# FX-NVBMP_rev_A.net
KiCad netlist of a schematic drawn in EAGLE
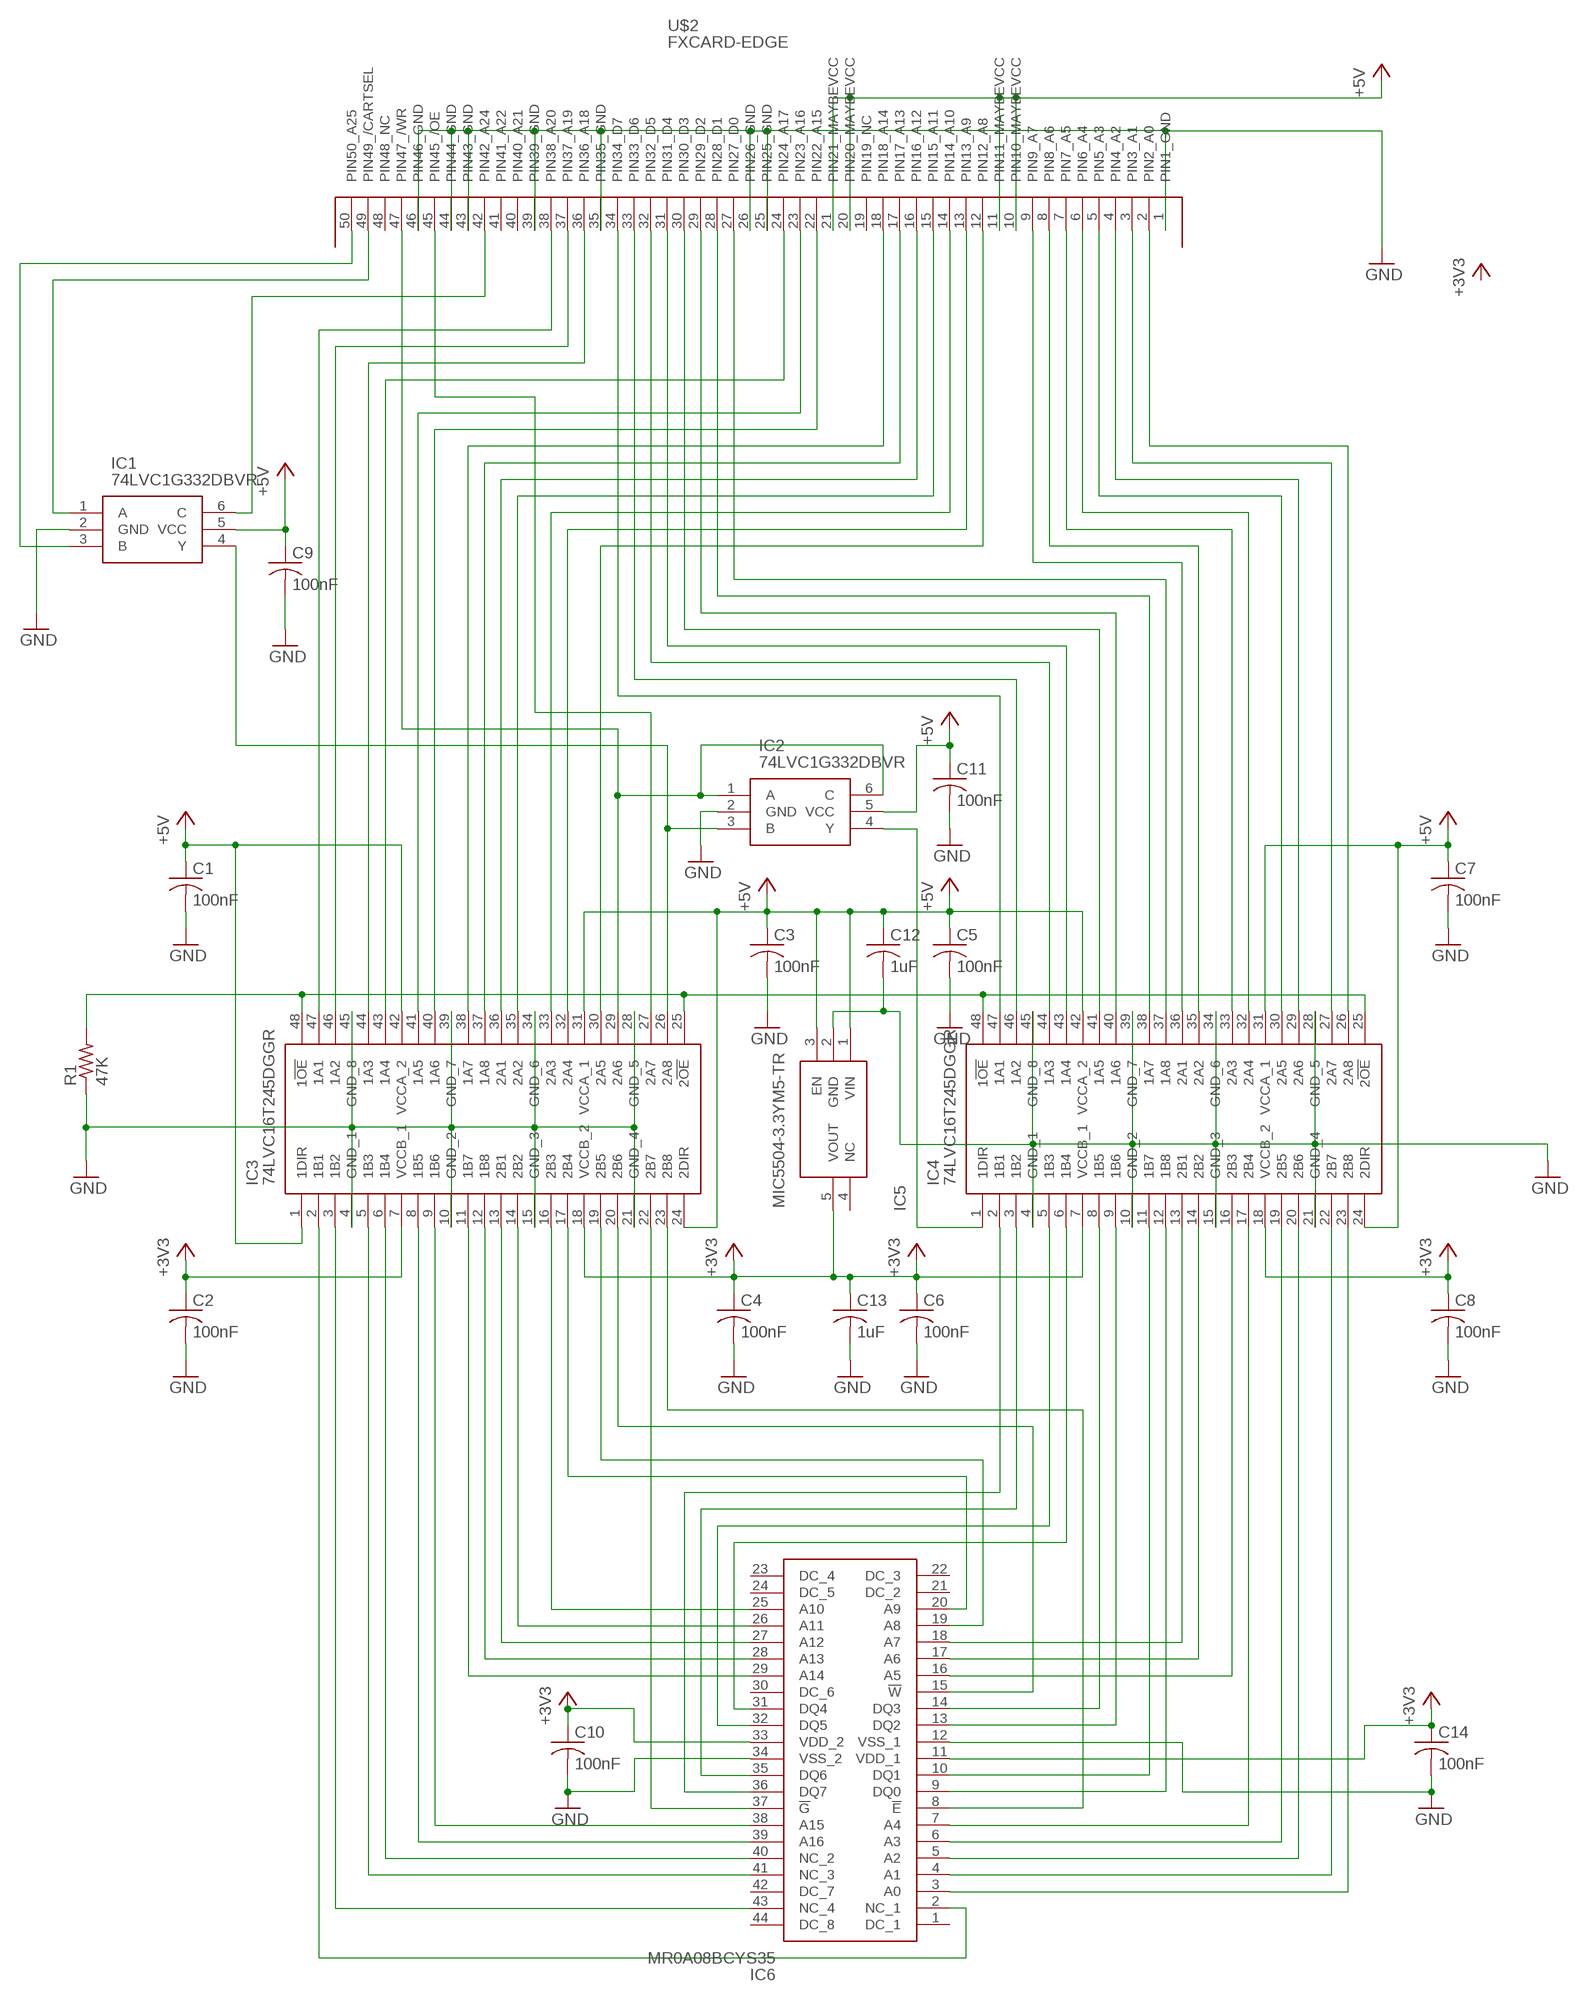
[diagram p0: schematic, sheet 1]

(export (version "E")
  (design (tool "Eeschema 10.0.6"))
  (components
    (comp (ref "C1")
      (value "100nF")
      (footprint "eagle-import:C0402")
      (libsource (lib "eagle-import") (part "C-USC0402"))
    )
    (comp (ref "C2")
      (value "100nF")
      (footprint "eagle-import:C0402")
      (libsource (lib "eagle-import") (part "C-USC0402"))
    )
    (comp (ref "C3")
      (value "100nF")
      (footprint "eagle-import:C0402")
      (libsource (lib "eagle-import") (part "C-USC0402"))
    )
    (comp (ref "C4")
      (value "100nF")
      (footprint "eagle-import:C0402")
      (libsource (lib "eagle-import") (part "C-USC0402"))
    )
    (comp (ref "C5")
      (value "100nF")
      (footprint "eagle-import:C0402")
      (libsource (lib "eagle-import") (part "C-USC0402"))
    )
    (comp (ref "C6")
      (value "100nF")
      (footprint "eagle-import:C0402")
      (libsource (lib "eagle-import") (part "C-USC0402"))
    )
    (comp (ref "C7")
      (value "100nF")
      (footprint "eagle-import:C0402")
      (libsource (lib "eagle-import") (part "C-USC0402"))
    )
    (comp (ref "C8")
      (value "100nF")
      (footprint "eagle-import:C0402")
      (libsource (lib "eagle-import") (part "C-USC0402"))
    )
    (comp (ref "C9")
      (value "100nF")
      (footprint "eagle-import:C0402")
      (libsource (lib "eagle-import") (part "C-USC0402"))
    )
    (comp (ref "C10")
      (value "100nF")
      (footprint "eagle-import:C0402")
      (libsource (lib "eagle-import") (part "C-USC0402"))
    )
    (comp (ref "C11")
      (value "100nF")
      (footprint "eagle-import:C0402")
      (libsource (lib "eagle-import") (part "C-USC0402"))
    )
    (comp (ref "C12")
      (value "1uF")
      (footprint "eagle-import:C0402")
      (libsource (lib "eagle-import") (part "C-USC0402"))
    )
    (comp (ref "C13")
      (value "1uF")
      (footprint "eagle-import:C0402")
      (libsource (lib "eagle-import") (part "C-USC0402"))
    )
    (comp (ref "C14")
      (value "100nF")
      (footprint "eagle-import:C0402")
      (libsource (lib "eagle-import") (part "C-USC0402"))
    )
    (comp (ref "IC1")
      (value "74LVC1G332DBVR")
      (footprint "eagle-import:SOT95P280X145-6N")
      (libsource (lib "eagle-import") (part "74LVC1G332DBVR"))
    )
    (comp (ref "IC2")
      (value "74LVC1G332DBVR")
      (footprint "eagle-import:SOT95P280X145-6N")
      (libsource (lib "eagle-import") (part "74LVC1G332DBVR"))
    )
    (comp (ref "IC3")
      (value "74LVC16T245DGGR")
      (footprint "eagle-import:SOP50P810X120-48N")
      (libsource (lib "eagle-import") (part "74LVC16T245DGGR"))
    )
    (comp (ref "IC4")
      (value "74LVC16T245DGGR")
      (footprint "eagle-import:SOP50P810X120-48N")
      (libsource (lib "eagle-import") (part "74LVC16T245DGGR"))
    )
    (comp (ref "IC5")
      (value "MIC5504-3.3YM5-TR")
      (footprint "eagle-import:SOT95P280X145-5N")
      (fields (field (name "MOUSER_PART_NUMBER") "998-MIC5504-3.3YM5TR"))
      (libsource (lib "eagle-import") (part "MIC5504-3.3YM5-TR"))
    )
    (comp (ref "IC6")
      (value "MR0A08BCYS35")
      (footprint "eagle-import:SOP80P1176X120-44N")
      (libsource (lib "eagle-import") (part "MR0A08BCYS35"))
    )
    (comp (ref "R1")
      (value "47K")
      (footprint "eagle-import:R0402")
      (libsource (lib "eagle-import") (part "R-US_R0402"))
    )
    (comp (ref "U$2")
      (value "FXCARD-EDGE")
      (footprint "eagle-import:FXCARD-EDGE")
      (libsource (lib "eagle-import") (part "FXCARD-EDGE"))
    )
  )
  (nets
    (net (code "1") (name "+3V3") (class "Default")
      (node (ref "C10") (pin "1") (pinfunction "1_1") (pintype "passive"))
      (node (ref "C13") (pin "1") (pinfunction "1_1") (pintype "passive"))
      (node (ref "C14") (pin "1") (pinfunction "1_1") (pintype "passive"))
      (node (ref "C2") (pin "1") (pinfunction "1_1") (pintype "passive"))
      (node (ref "C4") (pin "1") (pinfunction "1_1") (pintype "passive"))
      (node (ref "C6") (pin "1") (pinfunction "1_1") (pintype "passive"))
      (node (ref "C8") (pin "1") (pinfunction "1_1") (pintype "passive"))
      (node (ref "IC3") (pin "18") (pinfunction "VCCB_2_18") (pintype "bidirectional"))
      (node (ref "IC3") (pin "7") (pinfunction "VCCB_1_7") (pintype "bidirectional"))
      (node (ref "IC4") (pin "18") (pinfunction "VCCB_2_18") (pintype "bidirectional"))
      (node (ref "IC4") (pin "7") (pinfunction "VCCB_1_7") (pintype "bidirectional"))
      (node (ref "IC5") (pin "5") (pinfunction "VOUT_5") (pintype "bidirectional"))
      (node (ref "IC6") (pin "11") (pinfunction "VDD_1_11") (pintype "bidirectional"))
      (node (ref "IC6") (pin "33") (pinfunction "VDD_2_33") (pintype "bidirectional"))
    )
    (net (code "2") (name "+5V") (class "Default")
      (node (ref "C1") (pin "1") (pinfunction "1_1") (pintype "passive"))
      (node (ref "C11") (pin "1") (pinfunction "1_1") (pintype "passive"))
      (node (ref "C12") (pin "1") (pinfunction "1_1") (pintype "passive"))
      (node (ref "C3") (pin "1") (pinfunction "1_1") (pintype "passive"))
      (node (ref "C5") (pin "1") (pinfunction "1_1") (pintype "passive"))
      (node (ref "C7") (pin "1") (pinfunction "1_1") (pintype "passive"))
      (node (ref "C9") (pin "1") (pinfunction "1_1") (pintype "passive"))
      (node (ref "IC1") (pin "5") (pinfunction "VCC_5") (pintype "bidirectional"))
      (node (ref "IC2") (pin "5") (pinfunction "VCC_5") (pintype "bidirectional"))
      (node (ref "IC3") (pin "1") (pinfunction "1DIR_1") (pintype "bidirectional"))
      (node (ref "IC3") (pin "24") (pinfunction "2DIR_24") (pintype "bidirectional"))
      (node (ref "IC3") (pin "31") (pinfunction "VCCA_1_31") (pintype "bidirectional"))
      (node (ref "IC3") (pin "42") (pinfunction "VCCA_2_42") (pintype "bidirectional"))
      (node (ref "IC4") (pin "24") (pinfunction "2DIR_24") (pintype "bidirectional"))
      (node (ref "IC4") (pin "31") (pinfunction "VCCA_1_31") (pintype "bidirectional"))
      (node (ref "IC4") (pin "42") (pinfunction "VCCA_2_42") (pintype "bidirectional"))
      (node (ref "IC5") (pin "1") (pinfunction "VIN_1") (pintype "bidirectional"))
      (node (ref "IC5") (pin "3") (pinfunction "EN_3") (pintype "bidirectional"))
      (node (ref "U$2") (pin "10") (pinfunction "PIN10_MAYBEVCC_10") (pintype "bidirectional"))
      (node (ref "U$2") (pin "11") (pinfunction "PIN11_MAYBEVCC_11") (pintype "bidirectional"))
      (node (ref "U$2") (pin "20") (pinfunction "PIN20_MAYBEVCC_20") (pintype "bidirectional"))
      (node (ref "U$2") (pin "21") (pinfunction "PIN21_MAYBEVCC_21") (pintype "bidirectional"))
    )
    (net (code "3") (name "GND") (class "Default")
      (node (ref "C1") (pin "2") (pinfunction "2_2") (pintype "passive"))
      (node (ref "C10") (pin "2") (pinfunction "2_2") (pintype "passive"))
      (node (ref "C11") (pin "2") (pinfunction "2_2") (pintype "passive"))
      (node (ref "C12") (pin "2") (pinfunction "2_2") (pintype "passive"))
      (node (ref "C13") (pin "2") (pinfunction "2_2") (pintype "passive"))
      (node (ref "C14") (pin "2") (pinfunction "2_2") (pintype "passive"))
      (node (ref "C2") (pin "2") (pinfunction "2_2") (pintype "passive"))
      (node (ref "C3") (pin "2") (pinfunction "2_2") (pintype "passive"))
      (node (ref "C4") (pin "2") (pinfunction "2_2") (pintype "passive"))
      (node (ref "C5") (pin "2") (pinfunction "2_2") (pintype "passive"))
      (node (ref "C6") (pin "2") (pinfunction "2_2") (pintype "passive"))
      (node (ref "C7") (pin "2") (pinfunction "2_2") (pintype "passive"))
      (node (ref "C8") (pin "2") (pinfunction "2_2") (pintype "passive"))
      (node (ref "C9") (pin "2") (pinfunction "2_2") (pintype "passive"))
      (node (ref "IC1") (pin "2") (pinfunction "GND_2") (pintype "bidirectional"))
      (node (ref "IC2") (pin "2") (pinfunction "GND_2") (pintype "bidirectional"))
      (node (ref "IC3") (pin "10") (pinfunction "GND_2_10") (pintype "bidirectional"))
      (node (ref "IC3") (pin "15") (pinfunction "GND_3_15") (pintype "bidirectional"))
      (node (ref "IC3") (pin "21") (pinfunction "GND_4_21") (pintype "bidirectional"))
      (node (ref "IC3") (pin "28") (pinfunction "GND_5_28") (pintype "bidirectional"))
      (node (ref "IC3") (pin "34") (pinfunction "GND_6_34") (pintype "bidirectional"))
      (node (ref "IC3") (pin "39") (pinfunction "GND_7_39") (pintype "bidirectional"))
      (node (ref "IC3") (pin "4") (pinfunction "GND_1_4") (pintype "bidirectional"))
      (node (ref "IC3") (pin "45") (pinfunction "GND_8_45") (pintype "bidirectional"))
      (node (ref "IC4") (pin "10") (pinfunction "GND_2_10") (pintype "bidirectional"))
      (node (ref "IC4") (pin "15") (pinfunction "GND_3_15") (pintype "bidirectional"))
      (node (ref "IC4") (pin "21") (pinfunction "GND_4_21") (pintype "bidirectional"))
      (node (ref "IC4") (pin "28") (pinfunction "GND_5_28") (pintype "bidirectional"))
      (node (ref "IC4") (pin "34") (pinfunction "GND_6_34") (pintype "bidirectional"))
      (node (ref "IC4") (pin "39") (pinfunction "GND_7_39") (pintype "bidirectional"))
      (node (ref "IC4") (pin "4") (pinfunction "GND_1_4") (pintype "bidirectional"))
      (node (ref "IC4") (pin "45") (pinfunction "GND_8_45") (pintype "bidirectional"))
      (node (ref "IC5") (pin "2") (pinfunction "GND_2") (pintype "bidirectional"))
      (node (ref "IC6") (pin "12") (pinfunction "VSS_1_12") (pintype "bidirectional"))
      (node (ref "IC6") (pin "34") (pinfunction "VSS_2_34") (pintype "bidirectional"))
      (node (ref "R1") (pin "1") (pinfunction "1_1") (pintype "passive"))
      (node (ref "U$2") (pin "1") (pinfunction "PIN1_GND_1") (pintype "power_in"))
      (node (ref "U$2") (pin "25") (pinfunction "PIN25_GND_25") (pintype "power_in"))
      (node (ref "U$2") (pin "26") (pinfunction "PIN26_GND_26") (pintype "power_in"))
      (node (ref "U$2") (pin "35") (pinfunction "PIN35_GND_35") (pintype "power_in"))
      (node (ref "U$2") (pin "39") (pinfunction "PIN39_GND_39") (pintype "power_in"))
      (node (ref "U$2") (pin "43") (pinfunction "PIN43_GND_43") (pintype "power_in"))
      (node (ref "U$2") (pin "44") (pinfunction "PIN44_GND_44") (pintype "power_in"))
      (node (ref "U$2") (pin "46") (pinfunction "PIN46_GND_46") (pintype "power_in"))
    )
    (net (code "4") (name "Net-(IC1-A)") (class "Default")
      (node (ref "IC1") (pin "1") (pinfunction "A_1") (pintype "bidirectional"))
      (node (ref "U$2") (pin "49") (pinfunction "PIN49_/CARTSEL_49") (pintype "bidirectional"))
    )
    (net (code "5") (name "Net-(IC1-B)") (class "Default")
      (node (ref "IC1") (pin "3") (pinfunction "B_3") (pintype "bidirectional"))
      (node (ref "U$2") (pin "50") (pinfunction "PIN50_A25_50") (pintype "bidirectional"))
    )
    (net (code "6") (name "Net-(IC1-C)") (class "Default")
      (node (ref "IC1") (pin "6") (pinfunction "C_6") (pintype "bidirectional"))
      (node (ref "U$2") (pin "42") (pinfunction "PIN42_A24_42") (pintype "bidirectional"))
    )
    (net (code "7") (name "Net-(IC1-Y)") (class "Default")
      (node (ref "IC1") (pin "4") (pinfunction "Y_4") (pintype "bidirectional"))
      (node (ref "IC2") (pin "3") (pinfunction "B_3") (pintype "bidirectional"))
      (node (ref "IC3") (pin "26") (pinfunction "2A8_26") (pintype "bidirectional"))
    )
    (net (code "8") (name "Net-(IC2-A)") (class "Default")
      (node (ref "IC2") (pin "1") (pinfunction "A_1") (pintype "bidirectional"))
      (node (ref "IC2") (pin "6") (pinfunction "C_6") (pintype "bidirectional"))
      (node (ref "IC3") (pin "29") (pinfunction "2A6_29") (pintype "bidirectional"))
      (node (ref "U$2") (pin "47") (pinfunction "PIN47_/WR_47") (pintype "bidirectional"))
    )
    (net (code "9") (name "Net-(IC2-Y)") (class "Default")
      (node (ref "IC2") (pin "4") (pinfunction "Y_4") (pintype "bidirectional"))
      (node (ref "IC4") (pin "1") (pinfunction "1DIR_1") (pintype "bidirectional"))
    )
    (net (code "10") (name "Net-(IC3-1A1)") (class "Default")
      (node (ref "IC3") (pin "47") (pinfunction "1A1_47") (pintype "bidirectional"))
      (node (ref "U$2") (pin "38") (pinfunction "PIN38_A20_38") (pintype "bidirectional"))
    )
    (net (code "11") (name "Net-(IC3-1A2)") (class "Default")
      (node (ref "IC3") (pin "46") (pinfunction "1A2_46") (pintype "bidirectional"))
      (node (ref "U$2") (pin "37") (pinfunction "PIN37_A19_37") (pintype "bidirectional"))
    )
    (net (code "12") (name "Net-(IC3-1A3)") (class "Default")
      (node (ref "IC3") (pin "44") (pinfunction "1A3_44") (pintype "bidirectional"))
      (node (ref "U$2") (pin "36") (pinfunction "PIN36_A18_36") (pintype "bidirectional"))
    )
    (net (code "13") (name "Net-(IC3-1A4)") (class "Default")
      (node (ref "IC3") (pin "43") (pinfunction "1A4_43") (pintype "bidirectional"))
      (node (ref "U$2") (pin "24") (pinfunction "PIN24_A17_24") (pintype "bidirectional"))
    )
    (net (code "14") (name "Net-(IC3-1A5)") (class "Default")
      (node (ref "IC3") (pin "41") (pinfunction "1A5_41") (pintype "bidirectional"))
      (node (ref "U$2") (pin "23") (pinfunction "PIN23_A16_23") (pintype "bidirectional"))
    )
    (net (code "15") (name "Net-(IC3-1A6)") (class "Default")
      (node (ref "IC3") (pin "40") (pinfunction "1A6_40") (pintype "bidirectional"))
      (node (ref "U$2") (pin "22") (pinfunction "PIN22_A15_22") (pintype "bidirectional"))
    )
    (net (code "16") (name "Net-(IC3-1A7)") (class "Default")
      (node (ref "IC3") (pin "38") (pinfunction "1A7_38") (pintype "bidirectional"))
      (node (ref "U$2") (pin "18") (pinfunction "PIN18_A14_18") (pintype "bidirectional"))
    )
    (net (code "17") (name "Net-(IC3-1A8)") (class "Default")
      (node (ref "IC3") (pin "37") (pinfunction "1A8_37") (pintype "bidirectional"))
      (node (ref "U$2") (pin "17") (pinfunction "PIN17_A13_17") (pintype "bidirectional"))
    )
    (net (code "18") (name "Net-(IC3-1B1)") (class "Default")
      (node (ref "IC3") (pin "2") (pinfunction "1B1_2") (pintype "bidirectional"))
      (node (ref "IC6") (pin "2") (pinfunction "NC_1_2") (pintype "bidirectional"))
    )
    (net (code "19") (name "Net-(IC3-1B2)") (class "Default")
      (node (ref "IC3") (pin "3") (pinfunction "1B2_3") (pintype "bidirectional"))
      (node (ref "IC6") (pin "43") (pinfunction "NC_4_43") (pintype "bidirectional"))
    )
    (net (code "20") (name "Net-(IC3-1B3)") (class "Default")
      (node (ref "IC3") (pin "5") (pinfunction "1B3_5") (pintype "bidirectional"))
      (node (ref "IC6") (pin "41") (pinfunction "NC_3_41") (pintype "bidirectional"))
    )
    (net (code "21") (name "Net-(IC3-1B4)") (class "Default")
      (node (ref "IC3") (pin "6") (pinfunction "1B4_6") (pintype "bidirectional"))
      (node (ref "IC6") (pin "40") (pinfunction "NC_2_40") (pintype "bidirectional"))
    )
    (net (code "22") (name "Net-(IC3-1B5)") (class "Default")
      (node (ref "IC3") (pin "8") (pinfunction "1B5_8") (pintype "bidirectional"))
      (node (ref "IC6") (pin "39") (pinfunction "A16_39") (pintype "bidirectional"))
    )
    (net (code "23") (name "Net-(IC3-1B6)") (class "Default")
      (node (ref "IC3") (pin "9") (pinfunction "1B6_9") (pintype "bidirectional"))
      (node (ref "IC6") (pin "38") (pinfunction "A15_38") (pintype "bidirectional"))
    )
    (net (code "24") (name "Net-(IC3-1B7)") (class "Default")
      (node (ref "IC3") (pin "11") (pinfunction "1B7_11") (pintype "bidirectional"))
      (node (ref "IC6") (pin "29") (pinfunction "A14_29") (pintype "bidirectional"))
    )
    (net (code "25") (name "Net-(IC3-1B8)") (class "Default")
      (node (ref "IC3") (pin "12") (pinfunction "1B8_12") (pintype "bidirectional"))
      (node (ref "IC6") (pin "28") (pinfunction "A13_28") (pintype "bidirectional"))
    )
    (net (code "26") (name "Net-(IC3-1~{OE})") (class "Default")
      (node (ref "IC3") (pin "25") (pinfunction "2~{OE}_25") (pintype "bidirectional"))
      (node (ref "IC3") (pin "48") (pinfunction "1~{OE}_48") (pintype "bidirectional"))
      (node (ref "IC4") (pin "25") (pinfunction "2~{OE}_25") (pintype "bidirectional"))
      (node (ref "IC4") (pin "48") (pinfunction "1~{OE}_48") (pintype "bidirectional"))
      (node (ref "R1") (pin "2") (pinfunction "2_2") (pintype "passive"))
    )
    (net (code "27") (name "Net-(IC3-2A1)") (class "Default")
      (node (ref "IC3") (pin "36") (pinfunction "2A1_36") (pintype "bidirectional"))
      (node (ref "U$2") (pin "16") (pinfunction "PIN16_A12_16") (pintype "bidirectional"))
    )
    (net (code "28") (name "Net-(IC3-2A2)") (class "Default")
      (node (ref "IC3") (pin "35") (pinfunction "2A2_35") (pintype "bidirectional"))
      (node (ref "U$2") (pin "15") (pinfunction "PIN15_A11_15") (pintype "bidirectional"))
    )
    (net (code "29") (name "Net-(IC3-2A3)") (class "Default")
      (node (ref "IC3") (pin "33") (pinfunction "2A3_33") (pintype "bidirectional"))
      (node (ref "U$2") (pin "14") (pinfunction "PIN14_A10_14") (pintype "bidirectional"))
    )
    (net (code "30") (name "Net-(IC3-2A4)") (class "Default")
      (node (ref "IC3") (pin "32") (pinfunction "2A4_32") (pintype "bidirectional"))
      (node (ref "U$2") (pin "13") (pinfunction "PIN13_A9_13") (pintype "bidirectional"))
    )
    (net (code "31") (name "Net-(IC3-2A5)") (class "Default")
      (node (ref "IC3") (pin "30") (pinfunction "2A5_30") (pintype "bidirectional"))
      (node (ref "U$2") (pin "12") (pinfunction "PIN12_A8_12") (pintype "bidirectional"))
    )
    (net (code "32") (name "Net-(IC3-2A7)") (class "Default")
      (node (ref "IC3") (pin "27") (pinfunction "2A7_27") (pintype "bidirectional"))
      (node (ref "U$2") (pin "45") (pinfunction "PIN45_/OE_45") (pintype "bidirectional"))
    )
    (net (code "33") (name "Net-(IC3-2B1)") (class "Default")
      (node (ref "IC3") (pin "13") (pinfunction "2B1_13") (pintype "bidirectional"))
      (node (ref "IC6") (pin "27") (pinfunction "A12_27") (pintype "bidirectional"))
    )
    (net (code "34") (name "Net-(IC3-2B2)") (class "Default")
      (node (ref "IC3") (pin "14") (pinfunction "2B2_14") (pintype "bidirectional"))
      (node (ref "IC6") (pin "26") (pinfunction "A11_26") (pintype "bidirectional"))
    )
    (net (code "35") (name "Net-(IC3-2B3)") (class "Default")
      (node (ref "IC3") (pin "16") (pinfunction "2B3_16") (pintype "bidirectional"))
      (node (ref "IC6") (pin "25") (pinfunction "A10_25") (pintype "bidirectional"))
    )
    (net (code "36") (name "Net-(IC3-2B4)") (class "Default")
      (node (ref "IC3") (pin "17") (pinfunction "2B4_17") (pintype "bidirectional"))
      (node (ref "IC6") (pin "20") (pinfunction "A9_20") (pintype "bidirectional"))
    )
    (net (code "37") (name "Net-(IC3-2B5)") (class "Default")
      (node (ref "IC3") (pin "19") (pinfunction "2B5_19") (pintype "bidirectional"))
      (node (ref "IC6") (pin "19") (pinfunction "A8_19") (pintype "bidirectional"))
    )
    (net (code "38") (name "Net-(IC3-2B6)") (class "Default")
      (node (ref "IC3") (pin "20") (pinfunction "2B6_20") (pintype "bidirectional"))
      (node (ref "IC6") (pin "15") (pinfunction "~{W}_15") (pintype "bidirectional"))
    )
    (net (code "39") (name "Net-(IC3-2B7)") (class "Default")
      (node (ref "IC3") (pin "22") (pinfunction "2B7_22") (pintype "bidirectional"))
      (node (ref "IC6") (pin "37") (pinfunction "~{G}_37") (pintype "bidirectional"))
    )
    (net (code "40") (name "Net-(IC3-2B8)") (class "Default")
      (node (ref "IC3") (pin "23") (pinfunction "2B8_23") (pintype "bidirectional"))
      (node (ref "IC6") (pin "8") (pinfunction "~{E}_8") (pintype "bidirectional"))
    )
    (net (code "41") (name "Net-(IC4-1A1)") (class "Default")
      (node (ref "IC4") (pin "47") (pinfunction "1A1_47") (pintype "bidirectional"))
      (node (ref "U$2") (pin "34") (pinfunction "PIN34_D7_34") (pintype "bidirectional"))
    )
    (net (code "42") (name "Net-(IC4-1A2)") (class "Default")
      (node (ref "IC4") (pin "46") (pinfunction "1A2_46") (pintype "bidirectional"))
      (node (ref "U$2") (pin "33") (pinfunction "PIN33_D6_33") (pintype "bidirectional"))
    )
    (net (code "43") (name "Net-(IC4-1A3)") (class "Default")
      (node (ref "IC4") (pin "44") (pinfunction "1A3_44") (pintype "bidirectional"))
      (node (ref "U$2") (pin "32") (pinfunction "PIN32_D5_32") (pintype "bidirectional"))
    )
    (net (code "44") (name "Net-(IC4-1A4)") (class "Default")
      (node (ref "IC4") (pin "43") (pinfunction "1A4_43") (pintype "bidirectional"))
      (node (ref "U$2") (pin "31") (pinfunction "PIN31_D4_31") (pintype "bidirectional"))
    )
    (net (code "45") (name "Net-(IC4-1A5)") (class "Default")
      (node (ref "IC4") (pin "41") (pinfunction "1A5_41") (pintype "bidirectional"))
      (node (ref "U$2") (pin "30") (pinfunction "PIN30_D3_30") (pintype "bidirectional"))
    )
    (net (code "46") (name "Net-(IC4-1A6)") (class "Default")
      (node (ref "IC4") (pin "40") (pinfunction "1A6_40") (pintype "bidirectional"))
      (node (ref "U$2") (pin "29") (pinfunction "PIN29_D2_29") (pintype "bidirectional"))
    )
    (net (code "47") (name "Net-(IC4-1A7)") (class "Default")
      (node (ref "IC4") (pin "38") (pinfunction "1A7_38") (pintype "bidirectional"))
      (node (ref "U$2") (pin "28") (pinfunction "PIN28_D1_28") (pintype "bidirectional"))
    )
    (net (code "48") (name "Net-(IC4-1A8)") (class "Default")
      (node (ref "IC4") (pin "37") (pinfunction "1A8_37") (pintype "bidirectional"))
      (node (ref "U$2") (pin "27") (pinfunction "PIN27_D0_27") (pintype "bidirectional"))
    )
    (net (code "49") (name "Net-(IC4-1B1)") (class "Default")
      (node (ref "IC4") (pin "2") (pinfunction "1B1_2") (pintype "bidirectional"))
      (node (ref "IC6") (pin "36") (pinfunction "DQ7_36") (pintype "bidirectional"))
    )
    (net (code "50") (name "Net-(IC4-1B2)") (class "Default")
      (node (ref "IC4") (pin "3") (pinfunction "1B2_3") (pintype "bidirectional"))
      (node (ref "IC6") (pin "35") (pinfunction "DQ6_35") (pintype "bidirectional"))
    )
    (net (code "51") (name "Net-(IC4-1B3)") (class "Default")
      (node (ref "IC4") (pin "5") (pinfunction "1B3_5") (pintype "bidirectional"))
      (node (ref "IC6") (pin "32") (pinfunction "DQ5_32") (pintype "bidirectional"))
    )
    (net (code "52") (name "Net-(IC4-1B4)") (class "Default")
      (node (ref "IC4") (pin "6") (pinfunction "1B4_6") (pintype "bidirectional"))
      (node (ref "IC6") (pin "31") (pinfunction "DQ4_31") (pintype "bidirectional"))
    )
    (net (code "53") (name "Net-(IC4-1B5)") (class "Default")
      (node (ref "IC4") (pin "8") (pinfunction "1B5_8") (pintype "bidirectional"))
      (node (ref "IC6") (pin "14") (pinfunction "DQ3_14") (pintype "bidirectional"))
    )
    (net (code "54") (name "Net-(IC4-1B6)") (class "Default")
      (node (ref "IC4") (pin "9") (pinfunction "1B6_9") (pintype "bidirectional"))
      (node (ref "IC6") (pin "13") (pinfunction "DQ2_13") (pintype "bidirectional"))
    )
    (net (code "55") (name "Net-(IC4-1B7)") (class "Default")
      (node (ref "IC4") (pin "11") (pinfunction "1B7_11") (pintype "bidirectional"))
      (node (ref "IC6") (pin "10") (pinfunction "DQ1_10") (pintype "bidirectional"))
    )
    (net (code "56") (name "Net-(IC4-1B8)") (class "Default")
      (node (ref "IC4") (pin "12") (pinfunction "1B8_12") (pintype "bidirectional"))
      (node (ref "IC6") (pin "9") (pinfunction "DQ0_9") (pintype "bidirectional"))
    )
    (net (code "57") (name "Net-(IC4-2A1)") (class "Default")
      (node (ref "IC4") (pin "36") (pinfunction "2A1_36") (pintype "bidirectional"))
      (node (ref "U$2") (pin "9") (pinfunction "PIN9_A7_9") (pintype "bidirectional"))
    )
    (net (code "58") (name "Net-(IC4-2A2)") (class "Default")
      (node (ref "IC4") (pin "35") (pinfunction "2A2_35") (pintype "bidirectional"))
      (node (ref "U$2") (pin "8") (pinfunction "PIN8_A6_8") (pintype "bidirectional"))
    )
    (net (code "59") (name "Net-(IC4-2A3)") (class "Default")
      (node (ref "IC4") (pin "33") (pinfunction "2A3_33") (pintype "bidirectional"))
      (node (ref "U$2") (pin "7") (pinfunction "PIN7_A5_7") (pintype "bidirectional"))
    )
    (net (code "60") (name "Net-(IC4-2A4)") (class "Default")
      (node (ref "IC4") (pin "32") (pinfunction "2A4_32") (pintype "bidirectional"))
      (node (ref "U$2") (pin "6") (pinfunction "PIN6_A4_6") (pintype "bidirectional"))
    )
    (net (code "61") (name "Net-(IC4-2A5)") (class "Default")
      (node (ref "IC4") (pin "30") (pinfunction "2A5_30") (pintype "bidirectional"))
      (node (ref "U$2") (pin "5") (pinfunction "PIN5_A3_5") (pintype "bidirectional"))
    )
    (net (code "62") (name "Net-(IC4-2A6)") (class "Default")
      (node (ref "IC4") (pin "29") (pinfunction "2A6_29") (pintype "bidirectional"))
      (node (ref "U$2") (pin "4") (pinfunction "PIN4_A2_4") (pintype "bidirectional"))
    )
    (net (code "63") (name "Net-(IC4-2A7)") (class "Default")
      (node (ref "IC4") (pin "27") (pinfunction "2A7_27") (pintype "bidirectional"))
      (node (ref "U$2") (pin "3") (pinfunction "PIN3_A1_3") (pintype "bidirectional"))
    )
    (net (code "64") (name "Net-(IC4-2A8)") (class "Default")
      (node (ref "IC4") (pin "26") (pinfunction "2A8_26") (pintype "bidirectional"))
      (node (ref "U$2") (pin "2") (pinfunction "PIN2_A0_2") (pintype "bidirectional"))
    )
    (net (code "65") (name "Net-(IC4-2B1)") (class "Default")
      (node (ref "IC4") (pin "13") (pinfunction "2B1_13") (pintype "bidirectional"))
      (node (ref "IC6") (pin "18") (pinfunction "A7_18") (pintype "bidirectional"))
    )
    (net (code "66") (name "Net-(IC4-2B2)") (class "Default")
      (node (ref "IC4") (pin "14") (pinfunction "2B2_14") (pintype "bidirectional"))
      (node (ref "IC6") (pin "17") (pinfunction "A6_17") (pintype "bidirectional"))
    )
    (net (code "67") (name "Net-(IC4-2B3)") (class "Default")
      (node (ref "IC4") (pin "16") (pinfunction "2B3_16") (pintype "bidirectional"))
      (node (ref "IC6") (pin "16") (pinfunction "A5_16") (pintype "bidirectional"))
    )
    (net (code "68") (name "Net-(IC4-2B4)") (class "Default")
      (node (ref "IC4") (pin "17") (pinfunction "2B4_17") (pintype "bidirectional"))
      (node (ref "IC6") (pin "7") (pinfunction "A4_7") (pintype "bidirectional"))
    )
    (net (code "69") (name "Net-(IC4-2B5)") (class "Default")
      (node (ref "IC4") (pin "19") (pinfunction "2B5_19") (pintype "bidirectional"))
      (node (ref "IC6") (pin "6") (pinfunction "A3_6") (pintype "bidirectional"))
    )
    (net (code "70") (name "Net-(IC4-2B6)") (class "Default")
      (node (ref "IC4") (pin "20") (pinfunction "2B6_20") (pintype "bidirectional"))
      (node (ref "IC6") (pin "5") (pinfunction "A2_5") (pintype "bidirectional"))
    )
    (net (code "71") (name "Net-(IC4-2B7)") (class "Default")
      (node (ref "IC4") (pin "22") (pinfunction "2B7_22") (pintype "bidirectional"))
      (node (ref "IC6") (pin "4") (pinfunction "A1_4") (pintype "bidirectional"))
    )
    (net (code "72") (name "Net-(IC4-2B8)") (class "Default")
      (node (ref "IC4") (pin "23") (pinfunction "2B8_23") (pintype "bidirectional"))
      (node (ref "IC6") (pin "3") (pinfunction "A0_3") (pintype "bidirectional"))
    )
    (net (code "73") (name "unconnected-(IC5-NC-Pad4)") (class "Default")
      (node (ref "IC5") (pin "4") (pinfunction "NC_4") (pintype "no_connect"))
    )
    (net (code "74") (name "unconnected-(IC6-DC_1-Pad1)") (class "Default")
      (node (ref "IC6") (pin "1") (pinfunction "DC_1_1") (pintype "bidirectional"))
    )
    (net (code "75") (name "unconnected-(IC6-DC_2-Pad21)") (class "Default")
      (node (ref "IC6") (pin "21") (pinfunction "DC_2_21") (pintype "bidirectional"))
    )
    (net (code "76") (name "unconnected-(IC6-DC_3-Pad22)") (class "Default")
      (node (ref "IC6") (pin "22") (pinfunction "DC_3_22") (pintype "bidirectional"))
    )
    (net (code "77") (name "unconnected-(IC6-DC_4-Pad23)") (class "Default")
      (node (ref "IC6") (pin "23") (pinfunction "DC_4_23") (pintype "bidirectional"))
    )
    (net (code "78") (name "unconnected-(IC6-DC_5-Pad24)") (class "Default")
      (node (ref "IC6") (pin "24") (pinfunction "DC_5_24") (pintype "bidirectional"))
    )
    (net (code "79") (name "unconnected-(IC6-DC_6-Pad30)") (class "Default")
      (node (ref "IC6") (pin "30") (pinfunction "DC_6_30") (pintype "bidirectional"))
    )
    (net (code "80") (name "unconnected-(IC6-DC_7-Pad42)") (class "Default")
      (node (ref "IC6") (pin "42") (pinfunction "DC_7_42") (pintype "bidirectional"))
    )
    (net (code "81") (name "unconnected-(IC6-DC_8-Pad44)") (class "Default")
      (node (ref "IC6") (pin "44") (pinfunction "DC_8_44") (pintype "bidirectional"))
    )
    (net (code "82") (name "unconnected-(U$2-PIN19_NC-Pad19)") (class "Default")
      (node (ref "U$2") (pin "19") (pinfunction "PIN19_NC_19") (pintype "bidirectional"))
    )
    (net (code "83") (name "unconnected-(U$2-PIN40_A21-Pad40)") (class "Default")
      (node (ref "U$2") (pin "40") (pinfunction "PIN40_A21_40") (pintype "bidirectional"))
    )
    (net (code "84") (name "unconnected-(U$2-PIN41_A22-Pad41)") (class "Default")
      (node (ref "U$2") (pin "41") (pinfunction "PIN41_A22_41") (pintype "bidirectional"))
    )
    (net (code "85") (name "unconnected-(U$2-PIN48_NC-Pad48)") (class "Default")
      (node (ref "U$2") (pin "48") (pinfunction "PIN48_NC_48") (pintype "bidirectional"))
    )
  )
)
